# FT4232H-USB_to_UART.net
KiCad netlist of a schematic drawn in Altium Designer
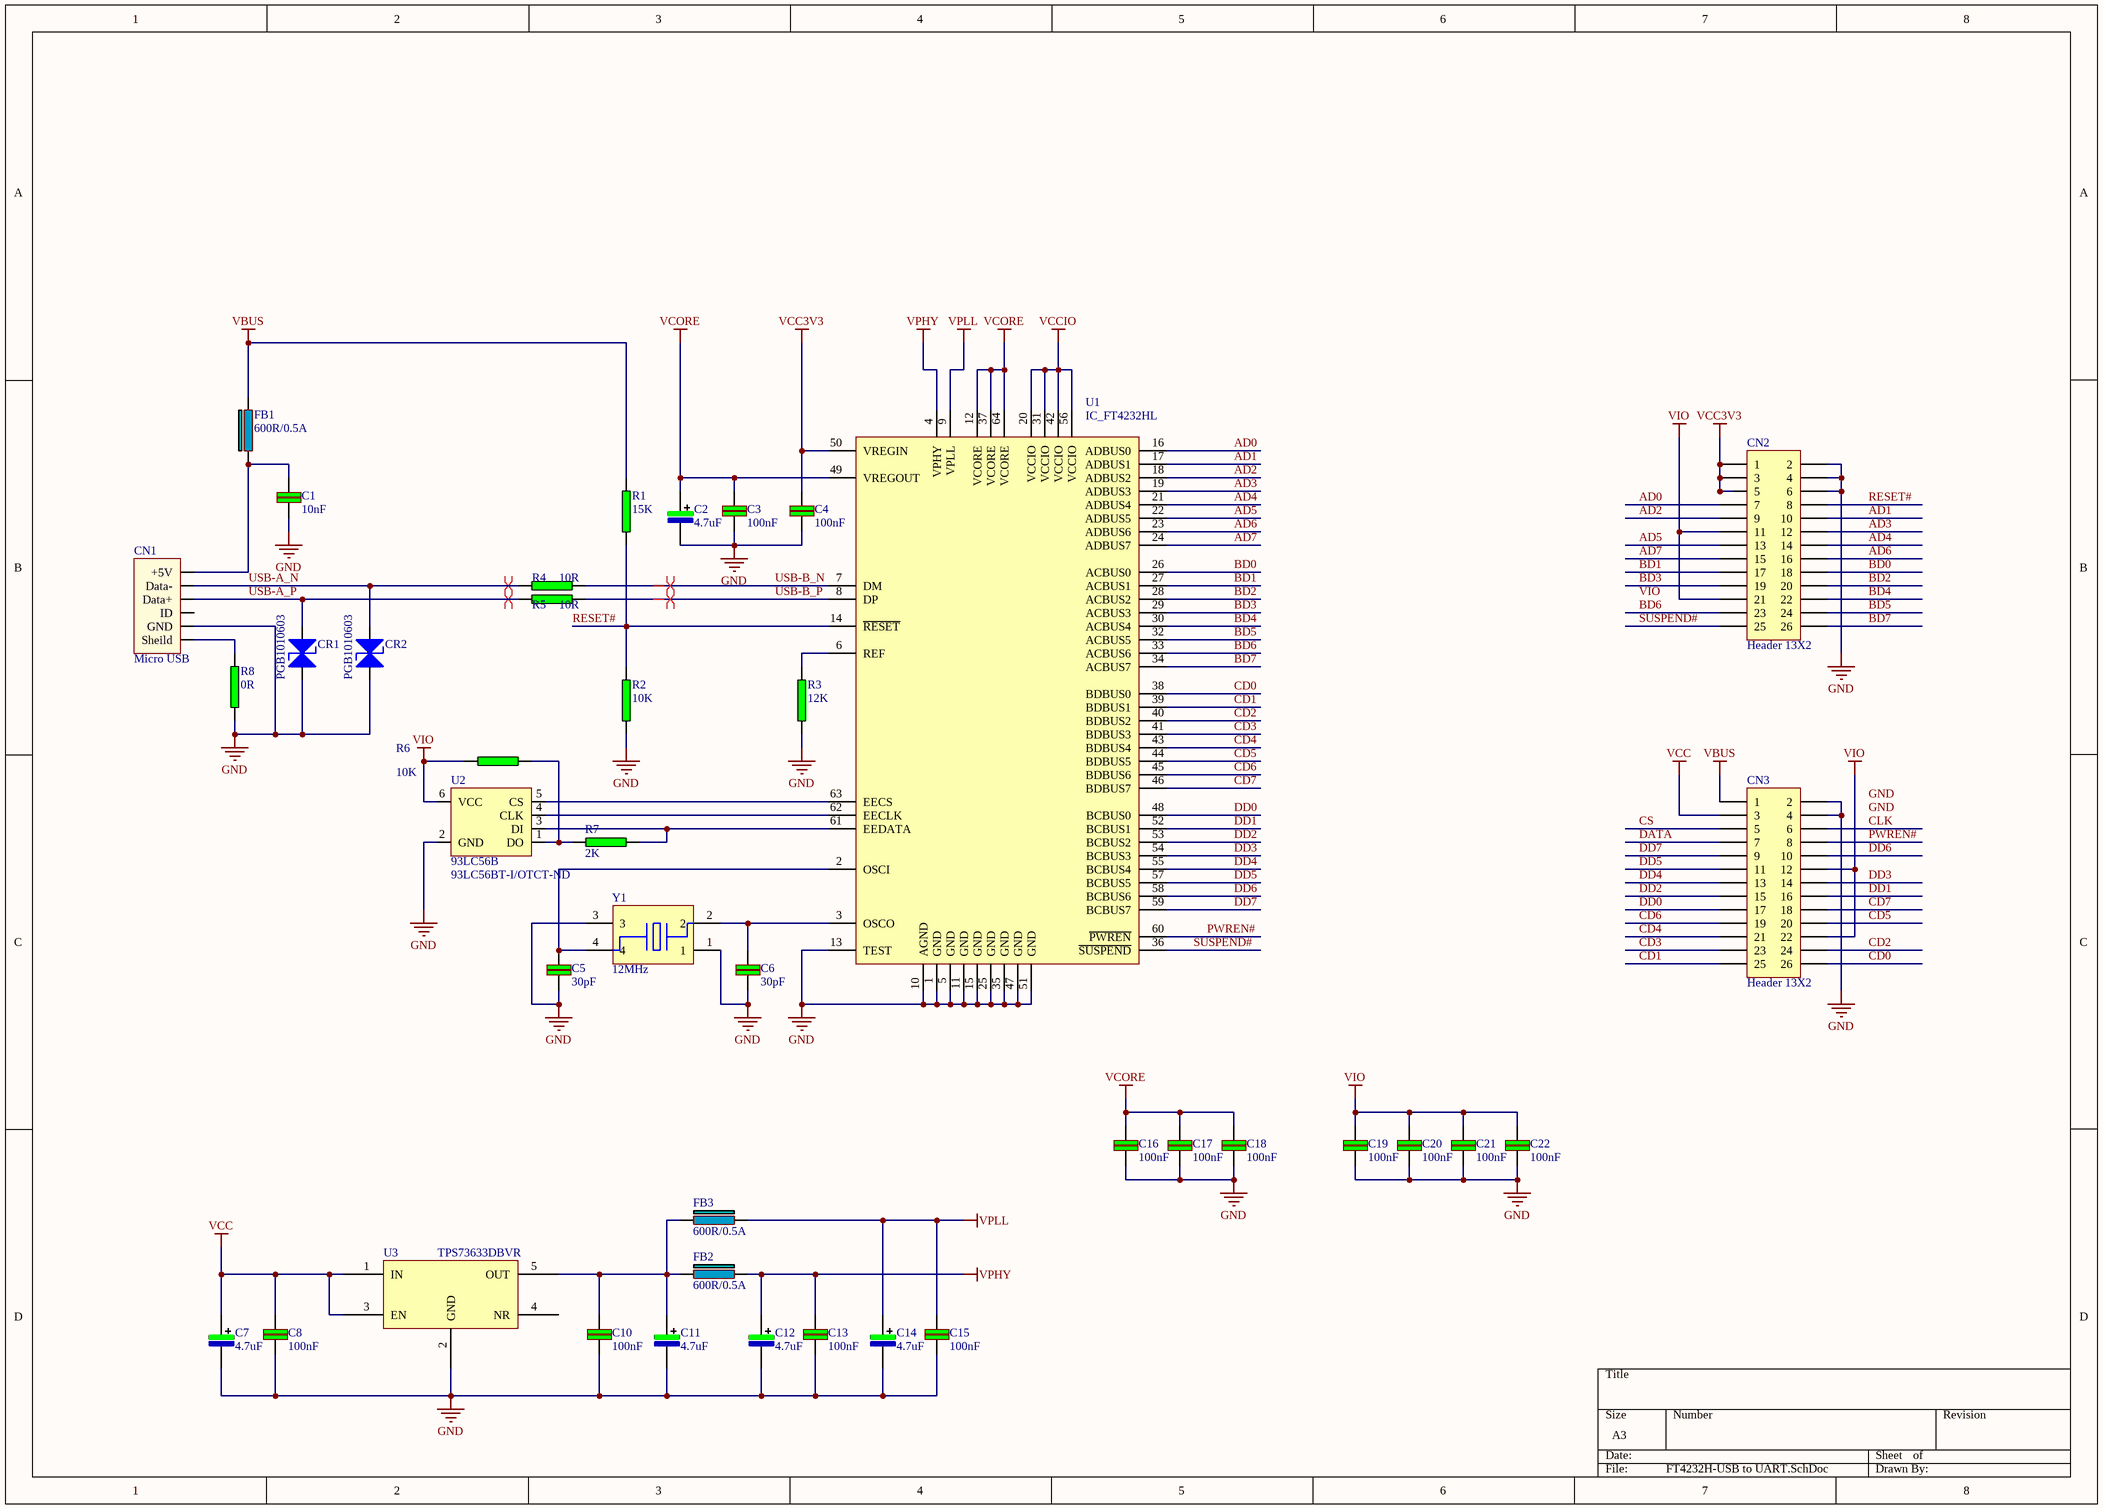
[diagram p0: FT4232H-USB to UART.SchDoc]

(export (version "E")
  (design (tool "Eeschema 10.0.6"))
  (components
    (comp (ref "C1")
      (value "10nF")
      (footprint "C0402(1005)")
      (description "Capacitor")
      (libsource (lib "SCH_C & R") (part "CAP"))
    )
    (comp (ref "C2")
      (value "4.7uF")
      (footprint "TANT_C1206(3216)")
      (description "Tantalum Capacitor")
      (libsource (lib "SCH_C & R") (part "ELECTRO"))
    )
    (comp (ref "C3")
      (value "100nF")
      (footprint "C0402(1005)")
      (description "Capacitor")
      (libsource (lib "SCH_C & R") (part "CAP"))
    )
    (comp (ref "C4")
      (value "100nF")
      (footprint "C0402(1005)")
      (description "Capacitor")
      (libsource (lib "SCH_C & R") (part "CAP"))
    )
    (comp (ref "C5")
      (value "30pF")
      (footprint "C0402(1005)")
      (description "Capacitor")
      (libsource (lib "SCH_C & R") (part "CAP"))
    )
    (comp (ref "C6")
      (value "30pF")
      (footprint "C0402(1005)")
      (description "Capacitor")
      (libsource (lib "SCH_C & R") (part "CAP"))
    )
    (comp (ref "C7")
      (value "4.7uF")
      (footprint "TANT_C1206(3216)")
      (description "Tantalum Capacitor")
      (libsource (lib "SCH_C & R") (part "ELECTRO"))
    )
    (comp (ref "C8")
      (value "100nF")
      (footprint "C0402(1005)")
      (description "Capacitor")
      (libsource (lib "SCH_C & R") (part "CAP"))
    )
    (comp (ref "C10")
      (value "100nF")
      (footprint "C0402(1005)")
      (description "Capacitor")
      (libsource (lib "SCH_C & R") (part "CAP"))
    )
    (comp (ref "C11")
      (value "4.7uF")
      (footprint "TANT_C1206(3216)")
      (description "Tantalum Capacitor")
      (libsource (lib "SCH_C & R") (part "ELECTRO"))
    )
    (comp (ref "C12")
      (value "4.7uF")
      (footprint "TANT_C1206(3216)")
      (description "Tantalum Capacitor")
      (libsource (lib "SCH_C & R") (part "ELECTRO"))
    )
    (comp (ref "C13")
      (value "100nF")
      (footprint "C0402(1005)")
      (description "Capacitor")
      (libsource (lib "SCH_C & R") (part "CAP"))
    )
    (comp (ref "C14")
      (value "4.7uF")
      (footprint "TANT_C1206(3216)")
      (description "Tantalum Capacitor")
      (libsource (lib "SCH_C & R") (part "ELECTRO"))
    )
    (comp (ref "C15")
      (value "100nF")
      (footprint "C0402(1005)")
      (description "Capacitor")
      (libsource (lib "SCH_C & R") (part "CAP"))
    )
    (comp (ref "C16")
      (value "100nF")
      (footprint "C0402(1005)")
      (description "Capacitor")
      (libsource (lib "SCH_C & R") (part "CAP"))
    )
    (comp (ref "C17")
      (value "100nF")
      (footprint "C0402(1005)")
      (description "Capacitor")
      (libsource (lib "SCH_C & R") (part "CAP"))
    )
    (comp (ref "C18")
      (value "100nF")
      (footprint "C0402(1005)")
      (description "Capacitor")
      (libsource (lib "SCH_C & R") (part "CAP"))
    )
    (comp (ref "C19")
      (value "100nF")
      (footprint "C0402(1005)")
      (description "Capacitor")
      (libsource (lib "SCH_C & R") (part "CAP"))
    )
    (comp (ref "C20")
      (value "100nF")
      (footprint "C0402(1005)")
      (description "Capacitor")
      (libsource (lib "SCH_C & R") (part "CAP"))
    )
    (comp (ref "C21")
      (value "100nF")
      (footprint "C0402(1005)")
      (description "Capacitor")
      (libsource (lib "SCH_C & R") (part "CAP"))
    )
    (comp (ref "C22")
      (value "100nF")
      (footprint "C0402(1005)")
      (description "Capacitor")
      (libsource (lib "SCH_C & R") (part "CAP"))
    )
    (comp (ref "CN1")
      (value "Micro USB")
      (footprint "MINI_USB")
      (description "Micro USB Connector")
      (libsource (lib "VIKO") (part "CON-USB_1"))
    )
    (comp (ref "CN2")
      (value "Header 13X2")
      (footprint "Pin Header 2x13 TH Pitch 2.54mm")
      (description "Header, 13-Pin, Dual row")
      (fields (field (name "PUBLISHER") "Altium Limited"))
      (libsource (lib "Miscellaneous Connectors") (part "Header 13X2"))
    )
    (comp (ref "CN3")
      (value "Header 13X2")
      (footprint "Pin Header 2x13 TH Pitch 2.54mm")
      (description "Header, 13-Pin, Dual row")
      (fields (field (name "PUBLISHER") "Altium Limited"))
      (libsource (lib "Miscellaneous Connectors") (part "Header 13X2"))
    )
    (comp (ref "CR1")
      (value "PGB1010603")
      (footprint "R0603(1608)")
      (description "TVS DIODE 24VWM 150VC 0603")
      (fields
        (field (name "MANUFACTURER") "Littelfuse Inc.")
        (field (name "MANUFACTURER PART NUMBER") "PGB1010603MR")
      )
      (libsource (lib "VIKO") (part "Diode_TVS_DS"))
    )
    (comp (ref "CR2")
      (value "PGB1010603")
      (footprint "R0603(1608)")
      (description "TVS DIODE 24VWM 150VC 0603")
      (fields
        (field (name "MANUFACTURER") "Littelfuse Inc.")
        (field (name "MANUFACTURER PART NUMBER") "PGB1010603MR")
      )
      (libsource (lib "VIKO") (part "Diode_TVS_DS"))
    )
    (comp (ref "FB1")
      (value "600R/0.5A")
      (footprint "R0603(1608)")
      (description "Ferrite Bead")
      (libsource (lib "") (part "L TYPE 1_1"))
    )
    (comp (ref "FB2")
      (value "600R/0.5A")
      (footprint "R0603(1608)")
      (description "Ferrite Bead")
      (libsource (lib "SCH_C & R") (part "L TYPE 1"))
    )
    (comp (ref "FB3")
      (value "600R/0.5A")
      (footprint "R0603(1608)")
      (description "Ferrite Bead")
      (libsource (lib "SCH_C & R") (part "L TYPE 1"))
    )
    (comp (ref "R1")
      (value "15K")
      (footprint "R0402(1005)")
      (description "Resistor")
      (libsource (lib "") (part "RES2_1"))
    )
    (comp (ref "R2")
      (value "10K")
      (footprint "R0402(1005)")
      (description "Resistor")
      (libsource (lib "") (part "RES2_1"))
    )
    (comp (ref "R3")
      (value "12K")
      (footprint "R0402(1005)")
      (description "Resistor")
      (libsource (lib "") (part "RES2_1"))
    )
    (comp (ref "R4")
      (value "10R")
      (footprint "R0402(1005)")
      (description "Resistor")
      (libsource (lib "SCH_C & R") (part "RES2"))
    )
    (comp (ref "R5")
      (value "10R")
      (footprint "R0402(1005)")
      (description "Resistor")
      (libsource (lib "SCH_C & R") (part "RES2"))
    )
    (comp (ref "R6")
      (value "10K")
      (footprint "R0402(1005)")
      (description "Resistor")
      (libsource (lib "") (part "RES2_2"))
    )
    (comp (ref "R7")
      (value "2K")
      (footprint "R0402(1005)")
      (description "Resistor")
      (libsource (lib "") (part "RES2_2"))
    )
    (comp (ref "R8")
      (value "0R")
      (footprint "R0402(1005)")
      (description "Resistor")
      (libsource (lib "") (part "RES2_1"))
    )
    (comp (ref "U1")
      (value "IC_FT4232HL")
      (footprint "LQFP-64")
      (description "Quad High Speed USB to Multipurpose UART/MPSSE")
      (libsource (lib "FTDI_SCH_Public") (part "IC_FT4232HL"))
    )
    (comp (ref "U2")
      (value "93LC56B")
      (footprint "SOT23-6")
      (description "IC EEPROM 2KBIT 2MHZ SOT23-6")
      (fields
        (field (name "SUPPLIER PART NUMBER 1") "93LC56BT-I/OTCT-ND")
        (field (name "MANUFACTURER") "Microchip Technology")
        (field (name "MANUFACTURER PART NUMBER") "93LC56BT-I/OT")
      )
      (libsource (lib "ali_lib") (part "93LC56B"))
    )
    (comp (ref "U3")
      (value "TPS73633DBVR")
      (footprint "SOT23-5")
      (description "IC REG LDO 3.3V 0.4A SOT23-5")
      (libsource (lib "ali_lib") (part "TPS736XX"))
    )
    (comp (ref "Y1")
      (value "12MHz")
      (footprint "XTAL_8Y")
      (description "XTAL  7S")
      (libsource (lib "SCHlib") (part "XTAL"))
    )
  )
  (nets
    (net (code "1") (name "/AD0") (class "Default")
      (node (ref "CN2") (pin "7") (pinfunction "7_7") (pintype "passive"))
      (node (ref "U1") (pin "16") (pinfunction "ADBUS0_16") (pintype "passive"))
    )
    (net (code "2") (name "/AD1") (class "Default")
      (node (ref "CN2") (pin "10") (pinfunction "10_10") (pintype "passive"))
      (node (ref "U1") (pin "17") (pinfunction "ADBUS1_17") (pintype "passive"))
    )
    (net (code "3") (name "/AD2") (class "Default")
      (node (ref "CN2") (pin "9") (pinfunction "9_9") (pintype "passive"))
      (node (ref "U1") (pin "18") (pinfunction "ADBUS2_18") (pintype "passive"))
    )
    (net (code "4") (name "/AD3") (class "Default")
      (node (ref "CN2") (pin "12") (pinfunction "12_12") (pintype "passive"))
      (node (ref "U1") (pin "19") (pinfunction "ADBUS3_19") (pintype "passive"))
    )
    (net (code "5") (name "/AD4") (class "Default")
      (node (ref "CN2") (pin "14") (pinfunction "14_14") (pintype "passive"))
      (node (ref "U1") (pin "21") (pinfunction "ADBUS4_21") (pintype "passive"))
    )
    (net (code "6") (name "/AD5") (class "Default")
      (node (ref "CN2") (pin "13") (pinfunction "13_13") (pintype "passive"))
      (node (ref "U1") (pin "22") (pinfunction "ADBUS5_22") (pintype "passive"))
    )
    (net (code "7") (name "/AD6") (class "Default")
      (node (ref "CN2") (pin "16") (pinfunction "16_16") (pintype "passive"))
      (node (ref "U1") (pin "23") (pinfunction "ADBUS6_23") (pintype "passive"))
    )
    (net (code "8") (name "/AD7") (class "Default")
      (node (ref "CN2") (pin "15") (pinfunction "15_15") (pintype "passive"))
      (node (ref "U1") (pin "24") (pinfunction "ADBUS7_24") (pintype "passive"))
    )
    (net (code "9") (name "/BD0") (class "Default")
      (node (ref "CN2") (pin "18") (pinfunction "18_18") (pintype "passive"))
      (node (ref "U1") (pin "26") (pinfunction "ACBUS0_26") (pintype "passive"))
    )
    (net (code "10") (name "/BD1") (class "Default")
      (node (ref "CN2") (pin "17") (pinfunction "17_17") (pintype "passive"))
      (node (ref "U1") (pin "27") (pinfunction "ACBUS1_27") (pintype "passive"))
    )
    (net (code "11") (name "/BD2") (class "Default")
      (node (ref "CN2") (pin "20") (pinfunction "20_20") (pintype "passive"))
      (node (ref "U1") (pin "28") (pinfunction "ACBUS2_28") (pintype "passive"))
    )
    (net (code "12") (name "/BD3") (class "Default")
      (node (ref "CN2") (pin "19") (pinfunction "19_19") (pintype "passive"))
      (node (ref "U1") (pin "29") (pinfunction "ACBUS3_29") (pintype "passive"))
    )
    (net (code "13") (name "/BD4") (class "Default")
      (node (ref "CN2") (pin "22") (pinfunction "22_22") (pintype "passive"))
      (node (ref "U1") (pin "30") (pinfunction "ACBUS4_30") (pintype "passive"))
    )
    (net (code "14") (name "/BD5") (class "Default")
      (node (ref "CN2") (pin "24") (pinfunction "24_24") (pintype "passive"))
      (node (ref "U1") (pin "32") (pinfunction "ACBUS5_32") (pintype "passive"))
    )
    (net (code "15") (name "/BD6") (class "Default")
      (node (ref "CN2") (pin "23") (pinfunction "23_23") (pintype "passive"))
      (node (ref "U1") (pin "33") (pinfunction "ACBUS6_33") (pintype "passive"))
    )
    (net (code "16") (name "/BD7") (class "Default")
      (node (ref "CN2") (pin "26") (pinfunction "26_26") (pintype "passive"))
      (node (ref "U1") (pin "34") (pinfunction "ACBUS7_34") (pintype "passive"))
    )
    (net (code "17") (name "/CD0") (class "Default")
      (node (ref "CN3") (pin "26") (pinfunction "26_26") (pintype "passive"))
      (node (ref "U1") (pin "38") (pinfunction "BDBUS0_38") (pintype "passive"))
    )
    (net (code "18") (name "/CD1") (class "Default")
      (node (ref "CN3") (pin "25") (pinfunction "25_25") (pintype "passive"))
      (node (ref "U1") (pin "39") (pinfunction "BDBUS1_39") (pintype "passive"))
    )
    (net (code "19") (name "/CD2") (class "Default")
      (node (ref "CN3") (pin "24") (pinfunction "24_24") (pintype "passive"))
      (node (ref "U1") (pin "40") (pinfunction "BDBUS2_40") (pintype "passive"))
    )
    (net (code "20") (name "/CD3") (class "Default")
      (node (ref "CN3") (pin "23") (pinfunction "23_23") (pintype "passive"))
      (node (ref "U1") (pin "41") (pinfunction "BDBUS3_41") (pintype "passive"))
    )
    (net (code "21") (name "/CD4") (class "Default")
      (node (ref "CN3") (pin "21") (pinfunction "21_21") (pintype "passive"))
      (node (ref "U1") (pin "43") (pinfunction "BDBUS4_43") (pintype "passive"))
    )
    (net (code "22") (name "/CD5") (class "Default")
      (node (ref "CN3") (pin "20") (pinfunction "20_20") (pintype "passive"))
      (node (ref "U1") (pin "44") (pinfunction "BDBUS5_44") (pintype "passive"))
    )
    (net (code "23") (name "/CD6") (class "Default")
      (node (ref "CN3") (pin "19") (pinfunction "19_19") (pintype "passive"))
      (node (ref "U1") (pin "45") (pinfunction "BDBUS6_45") (pintype "passive"))
    )
    (net (code "24") (name "/CD7") (class "Default")
      (node (ref "CN3") (pin "18") (pinfunction "18_18") (pintype "passive"))
      (node (ref "U1") (pin "46") (pinfunction "BDBUS7_46") (pintype "passive"))
    )
    (net (code "25") (name "/CLK") (class "Default")
      (node (ref "CN3") (pin "6") (pinfunction "6_6") (pintype "passive"))
    )
    (net (code "26") (name "/CS") (class "Default")
      (node (ref "CN3") (pin "5") (pinfunction "5_5") (pintype "passive"))
    )
    (net (code "27") (name "/DATA") (class "Default")
      (node (ref "CN3") (pin "7") (pinfunction "7_7") (pintype "passive"))
    )
    (net (code "28") (name "/DD0") (class "Default")
      (node (ref "CN3") (pin "17") (pinfunction "17_17") (pintype "passive"))
      (node (ref "U1") (pin "48") (pinfunction "BCBUS0_48") (pintype "passive"))
    )
    (net (code "29") (name "/DD1") (class "Default")
      (node (ref "CN3") (pin "16") (pinfunction "16_16") (pintype "passive"))
      (node (ref "U1") (pin "52") (pinfunction "BCBUS1_52") (pintype "passive"))
    )
    (net (code "30") (name "/DD2") (class "Default")
      (node (ref "CN3") (pin "15") (pinfunction "15_15") (pintype "passive"))
      (node (ref "U1") (pin "53") (pinfunction "BCBUS2_53") (pintype "passive"))
    )
    (net (code "31") (name "/DD3") (class "Default")
      (node (ref "CN3") (pin "14") (pinfunction "14_14") (pintype "passive"))
      (node (ref "U1") (pin "54") (pinfunction "BCBUS3_54") (pintype "passive"))
    )
    (net (code "32") (name "/DD4") (class "Default")
      (node (ref "CN3") (pin "13") (pinfunction "13_13") (pintype "passive"))
      (node (ref "U1") (pin "55") (pinfunction "BCBUS4_55") (pintype "passive"))
    )
    (net (code "33") (name "/DD5") (class "Default")
      (node (ref "CN3") (pin "11") (pinfunction "11_11") (pintype "passive"))
      (node (ref "U1") (pin "57") (pinfunction "BCBUS5_57") (pintype "passive"))
    )
    (net (code "34") (name "/DD6") (class "Default")
      (node (ref "CN3") (pin "10") (pinfunction "10_10") (pintype "passive"))
      (node (ref "U1") (pin "58") (pinfunction "BCBUS6_58") (pintype "passive"))
    )
    (net (code "35") (name "/DD7") (class "Default")
      (node (ref "CN3") (pin "9") (pinfunction "9_9") (pintype "passive"))
      (node (ref "U1") (pin "59") (pinfunction "BCBUS7_59") (pintype "passive"))
    )
    (net (code "36") (name "/PWREN#") (class "Default")
      (node (ref "CN3") (pin "8") (pinfunction "8_8") (pintype "passive"))
      (node (ref "U1") (pin "60") (pinfunction "~{PWREN}_60") (pintype "passive"))
    )
    (net (code "37") (name "/RESET#") (class "Default")
      (node (ref "CN2") (pin "8") (pinfunction "8_8") (pintype "passive"))
      (node (ref "R1") (pin "1") (pinfunction "1_1") (pintype "passive"))
      (node (ref "R2") (pin "2") (pinfunction "2_2") (pintype "passive"))
      (node (ref "U1") (pin "14") (pinfunction "~{RESET}_14") (pintype "passive"))
    )
    (net (code "38") (name "/SUSPEND#") (class "Default")
      (node (ref "CN2") (pin "25") (pinfunction "25_25") (pintype "passive"))
      (node (ref "U1") (pin "36") (pinfunction "~{SUSPEND}_36") (pintype "passive"))
    )
    (net (code "39") (name "/USB-A_N") (class "Default")
      (node (ref "CN1") (pin "2") (pinfunction "Data-_2") (pintype "passive"))
      (node (ref "CR2") (pin "1") (pinfunction "K_1") (pintype "passive"))
      (node (ref "R4") (pin "1") (pinfunction "1_1") (pintype "passive"))
    )
    (net (code "40") (name "/USB-A_P") (class "Default")
      (node (ref "CN1") (pin "3") (pinfunction "Data+_3") (pintype "passive"))
      (node (ref "CR1") (pin "1") (pinfunction "K_1") (pintype "passive"))
      (node (ref "R5") (pin "1") (pinfunction "1_1") (pintype "passive"))
    )
    (net (code "41") (name "/USB-B_N") (class "Default")
      (node (ref "R4") (pin "2") (pinfunction "2_2") (pintype "passive"))
      (node (ref "U1") (pin "7") (pinfunction "DM_7") (pintype "passive"))
    )
    (net (code "42") (name "/USB-B_P") (class "Default")
      (node (ref "R5") (pin "2") (pinfunction "2_2") (pintype "passive"))
      (node (ref "U1") (pin "8") (pinfunction "DP_8") (pintype "passive"))
    )
    (net (code "43") (name "GND") (class "Default")
      (node (ref "C1") (pin "2") (pinfunction "2_2") (pintype "passive"))
      (node (ref "C10") (pin "2") (pinfunction "2_2") (pintype "passive"))
      (node (ref "C11") (pin "2") (pinfunction "2_2") (pintype "passive"))
      (node (ref "C12") (pin "2") (pinfunction "2_2") (pintype "passive"))
      (node (ref "C13") (pin "2") (pinfunction "2_2") (pintype "passive"))
      (node (ref "C14") (pin "2") (pinfunction "2_2") (pintype "passive"))
      (node (ref "C15") (pin "2") (pinfunction "2_2") (pintype "passive"))
      (node (ref "C16") (pin "2") (pinfunction "2_2") (pintype "passive"))
      (node (ref "C17") (pin "2") (pinfunction "2_2") (pintype "passive"))
      (node (ref "C18") (pin "2") (pinfunction "2_2") (pintype "passive"))
      (node (ref "C19") (pin "2") (pinfunction "2_2") (pintype "passive"))
      (node (ref "C2") (pin "2") (pinfunction "2_2") (pintype "passive"))
      (node (ref "C20") (pin "2") (pinfunction "2_2") (pintype "passive"))
      (node (ref "C21") (pin "2") (pinfunction "2_2") (pintype "passive"))
      (node (ref "C22") (pin "2") (pinfunction "2_2") (pintype "passive"))
      (node (ref "C3") (pin "2") (pinfunction "2_2") (pintype "passive"))
      (node (ref "C4") (pin "2") (pinfunction "2_2") (pintype "passive"))
      (node (ref "C5") (pin "2") (pinfunction "2_2") (pintype "passive"))
      (node (ref "C6") (pin "2") (pinfunction "2_2") (pintype "passive"))
      (node (ref "C7") (pin "2") (pinfunction "2_2") (pintype "passive"))
      (node (ref "C8") (pin "2") (pinfunction "2_2") (pintype "passive"))
      (node (ref "CN1") (pin "5") (pinfunction "GND_5") (pintype "passive"))
      (node (ref "CN2") (pin "2") (pinfunction "2_2") (pintype "passive"))
      (node (ref "CN2") (pin "4") (pinfunction "4_4") (pintype "passive"))
      (node (ref "CN2") (pin "6") (pinfunction "6_6") (pintype "passive"))
      (node (ref "CN3") (pin "2") (pinfunction "2_2") (pintype "passive"))
      (node (ref "CN3") (pin "4") (pinfunction "4_4") (pintype "passive"))
      (node (ref "CR1") (pin "2") (pinfunction "A_2") (pintype "passive"))
      (node (ref "CR2") (pin "2") (pinfunction "A_2") (pintype "passive"))
      (node (ref "R2") (pin "1") (pinfunction "1_1") (pintype "passive"))
      (node (ref "R3") (pin "1") (pinfunction "1_1") (pintype "passive"))
      (node (ref "R8") (pin "1") (pinfunction "1_1") (pintype "passive"))
      (node (ref "U1") (pin "1") (pinfunction "GND_1") (pintype "passive"))
      (node (ref "U1") (pin "10") (pinfunction "AGND_10") (pintype "passive"))
      (node (ref "U1") (pin "11") (pinfunction "GND_11") (pintype "passive"))
      (node (ref "U1") (pin "13") (pinfunction "TEST_13") (pintype "passive"))
      (node (ref "U1") (pin "15") (pinfunction "GND_15") (pintype "passive"))
      (node (ref "U1") (pin "25") (pinfunction "GND_25") (pintype "passive"))
      (node (ref "U1") (pin "35") (pinfunction "GND_35") (pintype "passive"))
      (node (ref "U1") (pin "47") (pinfunction "GND_47") (pintype "passive"))
      (node (ref "U1") (pin "5") (pinfunction "GND_5") (pintype "passive"))
      (node (ref "U1") (pin "51") (pinfunction "GND_51") (pintype "passive"))
      (node (ref "U2") (pin "2") (pinfunction "GND_2") (pintype "passive"))
      (node (ref "U3") (pin "2") (pinfunction "GND_2") (pintype "passive"))
      (node (ref "Y1") (pin "1") (pinfunction "1_1") (pintype "passive"))
      (node (ref "Y1") (pin "3") (pinfunction "3_3") (pintype "passive"))
    )
    (net (code "44") (name "Net-(CN1-+5V)") (class "Default")
      (node (ref "C1") (pin "1") (pinfunction "1_1") (pintype "passive"))
      (node (ref "CN1") (pin "1") (pinfunction "+5V_1") (pintype "passive"))
      (node (ref "FB1") (pin "1") (pinfunction "1_1") (pintype "passive"))
    )
    (net (code "45") (name "Net-(CN1-Sheild)") (class "Default")
      (node (ref "CN1") (pin "6") (pinfunction "Sheild_6") (pintype "passive"))
      (node (ref "R8") (pin "2") (pinfunction "2_2") (pintype "passive"))
    )
    (net (code "46") (name "Net-(U1-EECLK)") (class "Default")
      (node (ref "U1") (pin "62") (pinfunction "EECLK_62") (pintype "passive"))
      (node (ref "U2") (pin "4") (pinfunction "CLK_4") (pintype "passive"))
    )
    (net (code "47") (name "Net-(U1-EECS)") (class "Default")
      (node (ref "U1") (pin "63") (pinfunction "EECS_63") (pintype "passive"))
      (node (ref "U2") (pin "5") (pinfunction "CS_5") (pintype "passive"))
    )
    (net (code "48") (name "Net-(U1-EEDATA)") (class "Default")
      (node (ref "R7") (pin "1") (pinfunction "1_1") (pintype "passive"))
      (node (ref "U1") (pin "61") (pinfunction "EEDATA_61") (pintype "passive"))
      (node (ref "U2") (pin "3") (pinfunction "DI_3") (pintype "passive"))
    )
    (net (code "49") (name "Net-(U1-OSCI)") (class "Default")
      (node (ref "C5") (pin "1") (pinfunction "1_1") (pintype "passive"))
      (node (ref "U1") (pin "2") (pinfunction "OSCI_2") (pintype "passive"))
      (node (ref "Y1") (pin "4") (pinfunction "4_4") (pintype "passive"))
    )
    (net (code "50") (name "Net-(U1-OSCO)") (class "Default")
      (node (ref "C6") (pin "1") (pinfunction "1_1") (pintype "passive"))
      (node (ref "U1") (pin "3") (pinfunction "OSCO_3") (pintype "passive"))
      (node (ref "Y1") (pin "2") (pinfunction "2_2") (pintype "passive"))
    )
    (net (code "51") (name "Net-(U1-REF)") (class "Default")
      (node (ref "R3") (pin "2") (pinfunction "2_2") (pintype "passive"))
      (node (ref "U1") (pin "6") (pinfunction "REF_6") (pintype "passive"))
    )
    (net (code "52") (name "Net-(U2-DO)") (class "Default")
      (node (ref "R6") (pin "1") (pinfunction "1_1") (pintype "passive"))
      (node (ref "R7") (pin "2") (pinfunction "2_2") (pintype "passive"))
      (node (ref "U2") (pin "1") (pinfunction "DO_1") (pintype "passive"))
    )
    (net (code "53") (name "Net-(U3-OUT)") (class "Default")
      (node (ref "C10") (pin "1") (pinfunction "1_1") (pintype "passive"))
      (node (ref "C11") (pin "1") (pinfunction "1_1") (pintype "passive"))
      (node (ref "FB2") (pin "1") (pinfunction "1_1") (pintype "passive"))
      (node (ref "FB3") (pin "1") (pinfunction "1_1") (pintype "passive"))
      (node (ref "U3") (pin "5") (pinfunction "OUT_5") (pintype "passive"))
    )
    (net (code "54") (name "VBUS") (class "Default")
      (node (ref "CN3") (pin "1") (pinfunction "1_1") (pintype "passive"))
      (node (ref "FB1") (pin "2") (pinfunction "2_2") (pintype "passive"))
      (node (ref "R1") (pin "2") (pinfunction "2_2") (pintype "passive"))
    )
    (net (code "55") (name "VCC") (class "Default")
      (node (ref "C7") (pin "1") (pinfunction "1_1") (pintype "passive"))
      (node (ref "C8") (pin "1") (pinfunction "1_1") (pintype "passive"))
      (node (ref "CN3") (pin "3") (pinfunction "3_3") (pintype "passive"))
      (node (ref "U3") (pin "1") (pinfunction "IN_1") (pintype "passive"))
      (node (ref "U3") (pin "3") (pinfunction "EN_3") (pintype "passive"))
    )
    (net (code "56") (name "VCC3V3") (class "Default")
      (node (ref "C4") (pin "1") (pinfunction "1_1") (pintype "passive"))
      (node (ref "CN2") (pin "1") (pinfunction "1_1") (pintype "passive"))
      (node (ref "CN2") (pin "3") (pinfunction "3_3") (pintype "passive"))
      (node (ref "CN2") (pin "5") (pinfunction "5_5") (pintype "passive"))
      (node (ref "U1") (pin "50") (pinfunction "VREGIN_50") (pintype "passive"))
    )
    (net (code "57") (name "VCCIO") (class "Default")
      (node (ref "U1") (pin "20") (pinfunction "VCCIO_20") (pintype "passive"))
      (node (ref "U1") (pin "31") (pinfunction "VCCIO_31") (pintype "passive"))
      (node (ref "U1") (pin "42") (pinfunction "VCCIO_42") (pintype "passive"))
      (node (ref "U1") (pin "56") (pinfunction "VCCIO_56") (pintype "passive"))
    )
    (net (code "58") (name "VCORE") (class "Default")
      (node (ref "C16") (pin "1") (pinfunction "1_1") (pintype "passive"))
      (node (ref "C17") (pin "1") (pinfunction "1_1") (pintype "passive"))
      (node (ref "C18") (pin "1") (pinfunction "1_1") (pintype "passive"))
      (node (ref "C2") (pin "1") (pinfunction "1_1") (pintype "passive"))
      (node (ref "C3") (pin "1") (pinfunction "1_1") (pintype "passive"))
      (node (ref "U1") (pin "12") (pinfunction "VCORE_12") (pintype "passive"))
      (node (ref "U1") (pin "37") (pinfunction "VCORE_37") (pintype "passive"))
      (node (ref "U1") (pin "49") (pinfunction "VREGOUT_49") (pintype "passive"))
      (node (ref "U1") (pin "64") (pinfunction "VCORE_64") (pintype "passive"))
    )
    (net (code "59") (name "VIO") (class "Default")
      (node (ref "C19") (pin "1") (pinfunction "1_1") (pintype "passive"))
      (node (ref "C20") (pin "1") (pinfunction "1_1") (pintype "passive"))
      (node (ref "C21") (pin "1") (pinfunction "1_1") (pintype "passive"))
      (node (ref "C22") (pin "1") (pinfunction "1_1") (pintype "passive"))
      (node (ref "CN2") (pin "11") (pinfunction "11_11") (pintype "passive"))
      (node (ref "CN2") (pin "21") (pinfunction "21_21") (pintype "passive"))
      (node (ref "CN3") (pin "12") (pinfunction "12_12") (pintype "passive"))
      (node (ref "CN3") (pin "22") (pinfunction "22_22") (pintype "passive"))
      (node (ref "R6") (pin "2") (pinfunction "2_2") (pintype "passive"))
      (node (ref "U2") (pin "6") (pinfunction "VCC_6") (pintype "passive"))
    )
    (net (code "60") (name "VPHY") (class "Default")
      (node (ref "C12") (pin "1") (pinfunction "1_1") (pintype "passive"))
      (node (ref "C13") (pin "1") (pinfunction "1_1") (pintype "passive"))
      (node (ref "FB2") (pin "2") (pinfunction "2_2") (pintype "passive"))
      (node (ref "U1") (pin "4") (pinfunction "VPHY_4") (pintype "passive"))
    )
    (net (code "61") (name "VPLL") (class "Default")
      (node (ref "C14") (pin "1") (pinfunction "1_1") (pintype "passive"))
      (node (ref "C15") (pin "1") (pinfunction "1_1") (pintype "passive"))
      (node (ref "FB3") (pin "2") (pinfunction "2_2") (pintype "passive"))
      (node (ref "U1") (pin "9") (pinfunction "VPLL_9") (pintype "passive"))
    )
    (net (code "62") (name "unconnected-(CN1-ID-Pad4)") (class "Default")
      (node (ref "CN1") (pin "4") (pinfunction "ID_4") (pintype "passive"))
    )
    (net (code "63") (name "unconnected-(U3-NR-Pad4)") (class "Default")
      (node (ref "U3") (pin "4") (pinfunction "NR_4") (pintype "passive"))
    )
  )
)
